# ConnMotor.net
KiCad netlist of a schematic drawn in Altium Designer
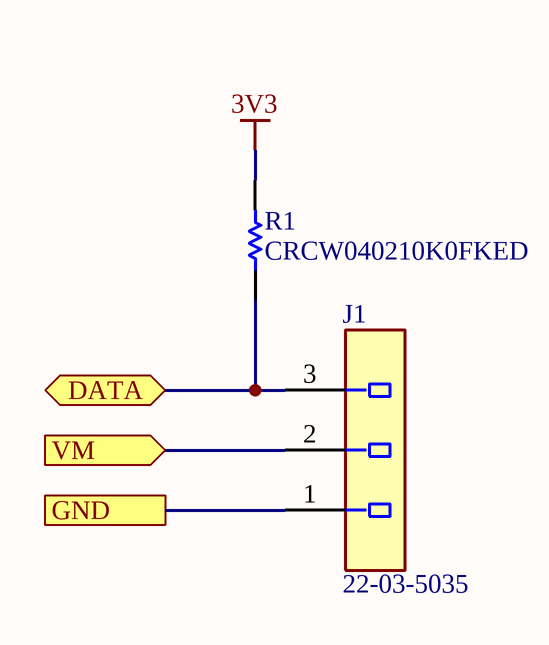
[diagram p0: ConnMotor.SchDoc]

(export (version "E")
  (design (tool "Eeschema 10.0.6"))
  (components
    (comp (ref "J1")
      (value "Conn_Molex_22-03-5035_eec")
      (footprint "Molex_22-03-5035_0")
      (description "CONN 3 Positions Header Connector 0.098\" (2.50mm) Through Hole Tin")
      (fields
        (field (name "PART NUMBER") "22-03-5035")
        (field (name "MANUFACTURER") "Molex")
        (field (name "MOUSER PART NUMBER") "538-22-03-5035")
      )
      (libsource (lib "Conn_Molex_22-03-5035_eec") (part "Conn_Molex_22-03-5035_eec"))
    )
    (comp (ref "R1")
      (value "CRCW040210K0FKED")
      (footprint "RESC1005X40X25NL05T05")
      (fields (field (name "MANUFACTURER") "Vishay Dale"))
      (libsource (lib "Altium Content Vault") (part "RES"))
    )
  )
  (nets
    (net (code "1") (name "/DATA") (class "Default")
      (node (ref "J1") (pin "3") (pinfunction "3_3") (pintype "passive"))
      (node (ref "R1") (pin "1") (pinfunction "1_1") (pintype "passive"))
    )
    (net (code "2") (name "/GND") (class "Default")
      (node (ref "J1") (pin "1") (pinfunction "1_1") (pintype "passive"))
    )
    (net (code "3") (name "/VM") (class "Default")
      (node (ref "J1") (pin "2") (pinfunction "2_2") (pintype "passive"))
    )
    (net (code "4") (name "3V3") (class "Default")
      (node (ref "R1") (pin "2") (pinfunction "2_2") (pintype "passive"))
    )
  )
)
